# RadFET.net
KiCad netlist of a schematic drawn in Altium Designer
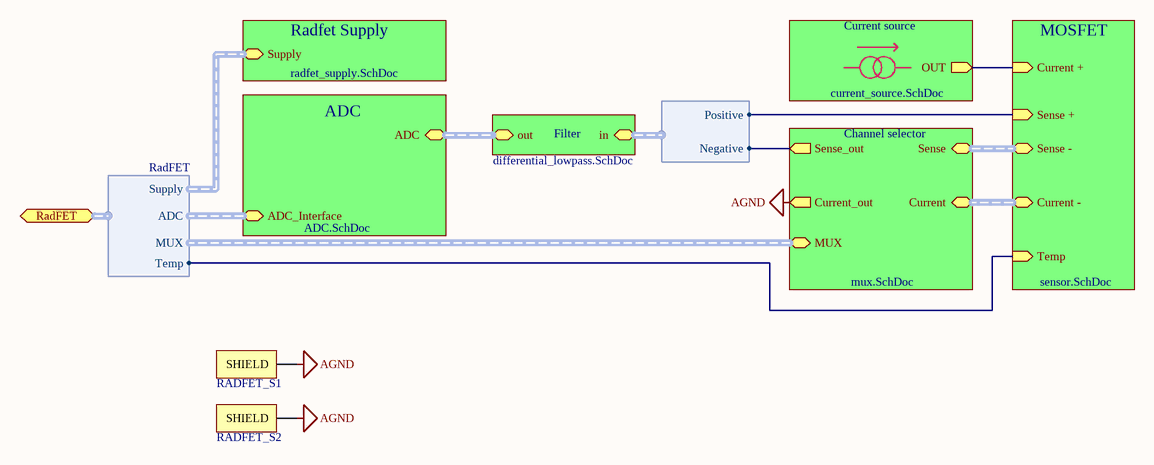
[diagram p0: RadFET.SchDoc]

(export (version "E")
  (design (tool "Eeschema 10.0.6"))
  (components
    (comp (ref "RADFET_S1")
      (value "BMI-S-203-F")
      (footprint "BMI-S-203-F_NO3D")
      (description "STANDARD SURFACE MOUNT SHIELD TWO-PIECE 26.21x26.21x5.08mm")
      (libsource (lib "rf") (part "BMI-S-203-F"))
    )
    (comp (ref "RADFET_S2")
      (value "BMI-S-203-F")
      (footprint "BMI-S-203-F_NO3D")
      (description "STANDARD SURFACE MOUNT SHIELD TWO-PIECE 26.21x26.21x5.08mm")
      (libsource (lib "rf") (part "BMI-S-203-F"))
    )
  )
  (nets
    (net (code "17") (name "AGND") (class "Default")
      (node (ref "RADFET_S1") (pin "0") (pinfunction "SHIELD_0") (pintype "passive"))
      (node (ref "RADFET_S2") (pin "0") (pinfunction "SHIELD_0") (pintype "passive"))
    )
  )
)
